# 24V_Multiphase_Buck.net
KiCad netlist of a schematic drawn in Altium Designer
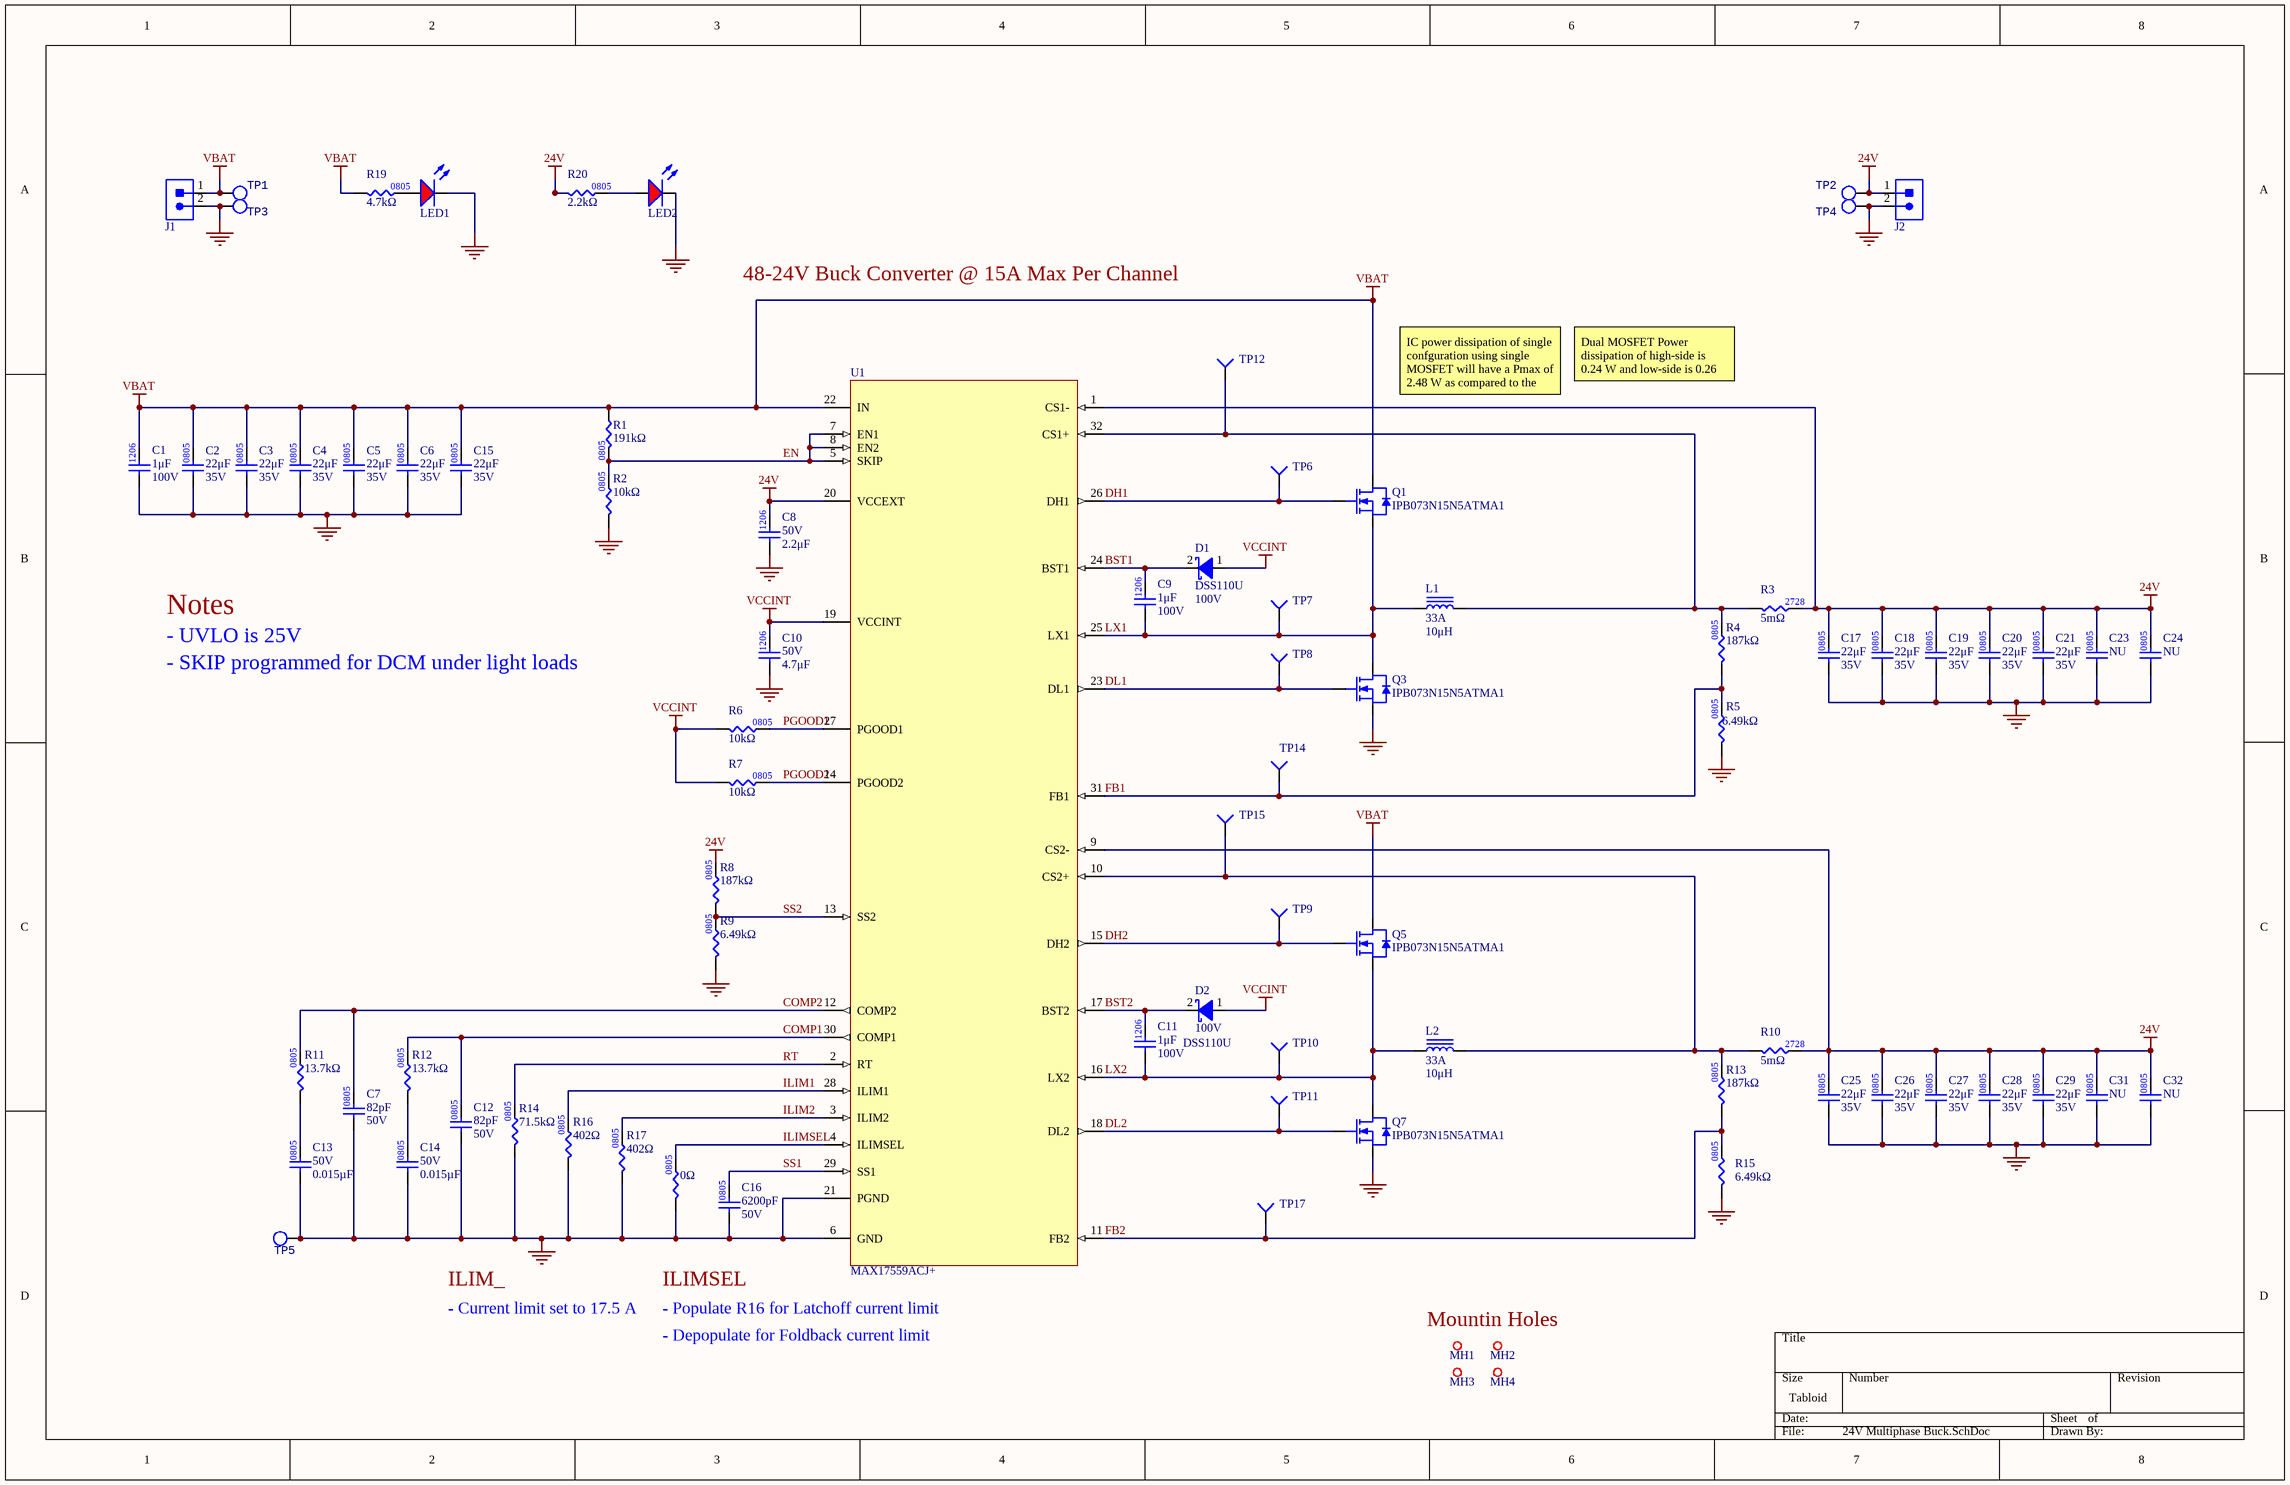
[diagram p0: 24V Multiphase Buck.SchDoc]

(export (version "E")
  (design (tool "Eeschema 10.0.6"))
  (components
    (comp (ref "C1")
      (value "1μF")
      (footprint "CAPC3216X190X50NL20T25")
      (description "CAP CER 1UF 100V X7R 1206")
      (fields (field (name "VOLTAGE RATING") "100V") (field (name "Comment") "CAP_1uF_100V_1206"))
      (libsource (lib "UWRT_Schematic_Library_2020") (part "CAP_1uF_100V_1206"))
    )
    (comp (ref "C2")
      (value "22μF")
      (footprint "CAP1206")
      (description "CAP CER 22UF 35V X5R 1206")
      (fields (field (name "VOLTAGE RATING") "35V") (field (name "Comment") "CAP_22uF_35V_1206"))
      (libsource (lib "UWRT_Schematic_Library_2020") (part "CAP_22uF_35V_1206"))
    )
    (comp (ref "C3")
      (value "22μF")
      (footprint "CAP1206")
      (description "CAP CER 22UF 35V X5R 1206")
      (fields (field (name "VOLTAGE RATING") "35V") (field (name "Comment") "CAP_22uF_35V_1206"))
      (libsource (lib "UWRT_Schematic_Library_2020") (part "CAP_22uF_35V_1206"))
    )
    (comp (ref "C4")
      (value "22μF")
      (footprint "CAP1206")
      (description "CAP CER 22UF 35V X5R 1206")
      (fields (field (name "VOLTAGE RATING") "35V") (field (name "Comment") "CAP_22uF_35V_1206"))
      (libsource (lib "UWRT_Schematic_Library_2020") (part "CAP_22uF_35V_1206"))
    )
    (comp (ref "C5")
      (value "22μF")
      (footprint "CAP1206")
      (description "CAP CER 22UF 35V X5R 1206")
      (fields (field (name "VOLTAGE RATING") "35V") (field (name "Comment") "CAP_22uF_35V_1206"))
      (libsource (lib "UWRT_Schematic_Library_2020") (part "CAP_22uF_35V_1206"))
    )
    (comp (ref "C6")
      (value "22μF")
      (footprint "CAP1206")
      (description "CAP CER 22UF 35V X5R 1206")
      (fields (field (name "VOLTAGE RATING") "35V") (field (name "Comment") "CAP_22uF_35V_1206"))
      (libsource (lib "UWRT_Schematic_Library_2020") (part "CAP_22uF_35V_1206"))
    )
    (comp (ref "C7")
      (value "82pF")
      (footprint "CAP0603")
      (description "CAP CER 82PF 50V C0G/NPO 0603")
      (fields (field (name "VOLTAGE RATING") "50V") (field (name "Comment") "CAP_82pF_50V_0603"))
      (libsource (lib "UWRT_Schematic_Library_2020") (part "CAP_82pF_50V_0603"))
    )
    (comp (ref "C8")
      (value "2.2μF")
      (footprint "CAP1206")
      (description "CAP CER 2.2UF 50V X7R 1206")
      (fields (field (name "VOLTAGE RATING") "50V") (field (name "Comment") "CAP_2.2uF_50V_1206"))
      (libsource (lib "UWRT_Schematic_Library_2020") (part "CAP_2.2uF_50V_1206"))
    )
    (comp (ref "C9")
      (value "1μF")
      (footprint "CAPC3216X190X50NL20T25")
      (description "CAP CER 1UF 100V X7R 1206")
      (fields (field (name "VOLTAGE RATING") "100V") (field (name "Comment") "CAP_1uF_100V_1206"))
      (libsource (lib "UWRT_Schematic_Library_2020") (part "CAP_1uF_100V_1206"))
    )
    (comp (ref "C10")
      (value "4.7μF")
      (footprint "CAP1206")
      (description "CAP CER 4.7UF 50V X7R 1206")
      (fields (field (name "VOLTAGE RATING") "50V") (field (name "Comment") "CAP_4.7uF_50V_1206"))
      (libsource (lib "UWRT_Schematic_Library_2020") (part "CAP_4.7uF_50V_1206"))
    )
    (comp (ref "C11")
      (value "1μF")
      (footprint "CAPC3216X190X50NL20T25")
      (description "CAP CER 1UF 100V X7R 1206")
      (fields (field (name "VOLTAGE RATING") "100V") (field (name "Comment") "CAP_1uF_100V_1206"))
      (libsource (lib "UWRT_Schematic_Library_2020") (part "CAP_1uF_100V_1206"))
    )
    (comp (ref "C12")
      (value "82pF")
      (footprint "CAP0603")
      (description "CAP CER 82PF 50V C0G/NPO 0603")
      (fields (field (name "VOLTAGE RATING") "50V") (field (name "Comment") "CAP_82pF_50V_0603"))
      (libsource (lib "UWRT_Schematic_Library_2020") (part "CAP_82pF_50V_0603"))
    )
    (comp (ref "C13")
      (value "0.015µF")
      (footprint "CAP0805")
      (description "CAP CER 0.015UF 50V C0G 0805")
      (fields (field (name "VOLTAGE RATING") "50V") (field (name "Comment") "CAP_0.015uF_50V_0805"))
      (libsource (lib "UWRT_Schematic_Library_2020") (part "CAP_0.015uF_50V_0805"))
    )
    (comp (ref "C14")
      (value "0.015µF")
      (footprint "CAP0805")
      (description "CAP CER 0.015UF 50V C0G 0805")
      (fields (field (name "VOLTAGE RATING") "50V") (field (name "Comment") "CAP_0.015uF_50V_0805"))
      (libsource (lib "UWRT_Schematic_Library_2020") (part "CAP_0.015uF_50V_0805"))
    )
    (comp (ref "C15")
      (value "22μF")
      (footprint "CAP1206")
      (description "CAP CER 22UF 35V X5R 1206")
      (fields (field (name "VOLTAGE RATING") "35V") (field (name "Comment") "CAP_22uF_35V_1206"))
      (libsource (lib "UWRT_Schematic_Library_2020") (part "CAP_22uF_35V_1206"))
    )
    (comp (ref "C16")
      (value "CAP_6200pF_50V_0805")
      (footprint "CAP0805")
      (description "CAP CER 6200PF 50V C0G/NP0 0805")
      (fields (field (name "CAPACITANCE") "6200pF") (field (name "VOLTAGE RATING") "50V"))
      (libsource (lib "UWRT_Schematic_Library_2020") (part "CAP_6200pF_50V_0805"))
    )
    (comp (ref "C17")
      (value "22μF")
      (footprint "CAP1206")
      (description "CAP CER 22UF 35V X5R 1206")
      (fields (field (name "VOLTAGE RATING") "35V") (field (name "Comment") "CAP_22uF_35V_1206"))
      (libsource (lib "UWRT_Schematic_Library_2020") (part "CAP_22uF_35V_1206"))
    )
    (comp (ref "C18")
      (value "22μF")
      (footprint "CAP1206")
      (description "CAP CER 22UF 35V X5R 1206")
      (fields (field (name "VOLTAGE RATING") "35V") (field (name "Comment") "CAP_22uF_35V_1206"))
      (libsource (lib "UWRT_Schematic_Library_2020") (part "CAP_22uF_35V_1206"))
    )
    (comp (ref "C19")
      (value "22μF")
      (footprint "CAP1206")
      (description "CAP CER 22UF 35V X5R 1206")
      (fields (field (name "VOLTAGE RATING") "35V") (field (name "Comment") "CAP_22uF_35V_1206"))
      (libsource (lib "UWRT_Schematic_Library_2020") (part "CAP_22uF_35V_1206"))
    )
    (comp (ref "C20")
      (value "22μF")
      (footprint "CAP1206")
      (description "CAP CER 22UF 35V X5R 1206")
      (fields (field (name "VOLTAGE RATING") "35V") (field (name "Comment") "CAP_22uF_35V_1206"))
      (libsource (lib "UWRT_Schematic_Library_2020") (part "CAP_22uF_35V_1206"))
    )
    (comp (ref "C21")
      (value "22μF")
      (footprint "CAP1206")
      (description "CAP CER 22UF 35V X5R 1206")
      (fields (field (name "VOLTAGE RATING") "35V") (field (name "Comment") "CAP_22uF_35V_1206"))
      (libsource (lib "UWRT_Schematic_Library_2020") (part "CAP_22uF_35V_1206"))
    )
    (comp (ref "C23")
      (value "NU")
      (footprint "CAP1206")
      (description "PLACEHOLDER CAPACITOR")
      (fields (field (name "Comment") "CAP_NU_1206"))
      (libsource (lib "UWRT_Schematic_Library_2020") (part "CAP_NU_1206"))
    )
    (comp (ref "C24")
      (value "NU")
      (footprint "CAP1206")
      (description "PLACEHOLDER CAPACITOR")
      (fields (field (name "Comment") "CAP_NU_1206"))
      (libsource (lib "UWRT_Schematic_Library_2020") (part "CAP_NU_1206"))
    )
    (comp (ref "C25")
      (value "22μF")
      (footprint "CAP1206")
      (description "CAP CER 22UF 35V X5R 1206")
      (fields (field (name "VOLTAGE RATING") "35V") (field (name "Comment") "CAP_22uF_35V_1206"))
      (libsource (lib "UWRT_Schematic_Library_2020") (part "CAP_22uF_35V_1206"))
    )
    (comp (ref "C26")
      (value "22μF")
      (footprint "CAP1206")
      (description "CAP CER 22UF 35V X5R 1206")
      (fields (field (name "VOLTAGE RATING") "35V") (field (name "Comment") "CAP_22uF_35V_1206"))
      (libsource (lib "UWRT_Schematic_Library_2020") (part "CAP_22uF_35V_1206"))
    )
    (comp (ref "C27")
      (value "22μF")
      (footprint "CAP1206")
      (description "CAP CER 22UF 35V X5R 1206")
      (fields (field (name "VOLTAGE RATING") "35V") (field (name "Comment") "CAP_22uF_35V_1206"))
      (libsource (lib "UWRT_Schematic_Library_2020") (part "CAP_22uF_35V_1206"))
    )
    (comp (ref "C28")
      (value "22μF")
      (footprint "CAP1206")
      (description "CAP CER 22UF 35V X5R 1206")
      (fields (field (name "VOLTAGE RATING") "35V") (field (name "Comment") "CAP_22uF_35V_1206"))
      (libsource (lib "UWRT_Schematic_Library_2020") (part "CAP_22uF_35V_1206"))
    )
    (comp (ref "C29")
      (value "22μF")
      (footprint "CAP1206")
      (description "CAP CER 22UF 35V X5R 1206")
      (fields (field (name "VOLTAGE RATING") "35V") (field (name "Comment") "CAP_22uF_35V_1206"))
      (libsource (lib "UWRT_Schematic_Library_2020") (part "CAP_22uF_35V_1206"))
    )
    (comp (ref "C31")
      (value "NU")
      (footprint "CAP1206")
      (description "PLACEHOLDER CAPACITOR")
      (fields (field (name "Comment") "CAP_NU_1206"))
      (libsource (lib "UWRT_Schematic_Library_2020") (part "CAP_NU_1206"))
    )
    (comp (ref "C32")
      (value "NU")
      (footprint "CAP1206")
      (description "PLACEHOLDER CAPACITOR")
      (fields (field (name "Comment") "CAP_NU_1206"))
      (libsource (lib "UWRT_Schematic_Library_2020") (part "CAP_NU_1206"))
    )
    (comp (ref "D1")
      (value "DIO_SCHOTTKY_100V_1A")
      (footprint "SOD-123FL")
      (description "DIODE SCHOTTKY 100V 1A SOD-123F")
      (fields (field (name "MANUFACTURER PART NUMBER 1") "DSS110U") (field (name "VR (MAX)") "100V"))
      (libsource (lib "UWRT_Schematic_Library_2020") (part "DIO_SCHOTTKY_100V_1A"))
    )
    (comp (ref "D2")
      (value "DIO_SCHOTTKY_100V_1A")
      (footprint "SOD-123FL")
      (description "DIODE SCHOTTKY 100V 1A SOD-123F")
      (fields (field (name "MANUFACTURER PART NUMBER 1") "DSS110U") (field (name "VR (MAX)") "100V"))
      (libsource (lib "UWRT_Schematic_Library_2020") (part "DIO_SCHOTTKY_100V_1A"))
    )
    (comp (ref "J1")
      (value "CON_2POS_SCREW_TERM")
      (footprint "CON_2POS_SCREW_TERM_65A")
      (description "PCB TERMINAL BLOCKS RISING CLAMP")
      (libsource (lib "UWRT_Schematic_Library_2020") (part "CON_2POS_SCREW_TERM_65A"))
    )
    (comp (ref "J2")
      (value "CON_2POS_SCREW_TERM")
      (footprint "CON_2POS_SCREW_TERM_65A")
      (description "PCB TERMINAL BLOCKS RISING CLAMP")
      (libsource (lib "") (part "CON_2POS_SCREW_TERM_65A_1"))
    )
    (comp (ref "L1")
      (value "IND_10uH_33A_SMD")
      (footprint "IND_B82559B7103A027")
      (description "FIXED IND 10UH 33A 1.92 MOHM SMD")
      (fields (field (name "CURRENT RATING") "33A") (field (name "INDUCTANCE") "10μH"))
      (libsource (lib "UWRT_Schematic_Library_2020") (part "IND_10uH_33A_SMD"))
    )
    (comp (ref "L2")
      (value "IND_10uH_33A_SMD")
      (footprint "IND_B82559B7103A027")
      (description "FIXED IND 10UH 33A 1.92 MOHM SMD")
      (fields (field (name "CURRENT RATING") "33A") (field (name "INDUCTANCE") "10μH"))
      (libsource (lib "UWRT_Schematic_Library_2020") (part "IND_10uH_33A_SMD"))
    )
    (comp (ref "LED1")
      (value "LED_RED")
      (footprint "LED_0805_RED")
      (description "LED RED DIFFUSED 0805 SMD")
      (libsource (lib "UWRT_Schematic_Library_2020") (part "LED_RED"))
    )
    (comp (ref "LED2")
      (value "LED_RED")
      (footprint "LED_0805_RED")
      (description "LED RED DIFFUSED 0805 SMD")
      (libsource (lib "UWRT_Schematic_Library_2020") (part "LED_RED"))
    )
    (comp (ref "MH1")
      (value "MOUNTING_HOLE_M3")
      (footprint "MOUNTING_HOLE_3mm")
      (libsource (lib "UWRT_Schematic_Library_2020") (part "MOUNTING_HOLE_M3"))
    )
    (comp (ref "MH2")
      (value "MOUNTING_HOLE_M3")
      (footprint "MOUNTING_HOLE_3mm")
      (libsource (lib "UWRT_Schematic_Library_2020") (part "MOUNTING_HOLE_M3"))
    )
    (comp (ref "MH3")
      (value "MOUNTING_HOLE_M3")
      (footprint "MOUNTING_HOLE_3mm")
      (libsource (lib "UWRT_Schematic_Library_2020") (part "MOUNTING_HOLE_M3"))
    )
    (comp (ref "MH4")
      (value "MOUNTING_HOLE_M3")
      (footprint "MOUNTING_HOLE_3mm")
      (libsource (lib "UWRT_Schematic_Library_2020") (part "MOUNTING_HOLE_M3"))
    )
    (comp (ref "Q1")
      (value "NMOS_150V_114A")
      (footprint "NMOS_DPAK263-3-2")
      (description "MOSFET N-CH 150V 114A TO263-3")
      (fields (field (name "MANUFACTURER PART NUMBER 1") "IPB073N15N5ATMA1"))
      (libsource (lib "UWRT_Schematic_Library_2020") (part "NMOS_150V_114A"))
    )
    (comp (ref "Q3")
      (value "NMOS_150V_114A")
      (footprint "NMOS_DPAK263-3-2")
      (description "MOSFET N-CH 150V 114A TO263-3")
      (fields (field (name "MANUFACTURER PART NUMBER 1") "IPB073N15N5ATMA1"))
      (libsource (lib "UWRT_Schematic_Library_2020") (part "NMOS_150V_114A"))
    )
    (comp (ref "Q5")
      (value "NMOS_150V_114A")
      (footprint "NMOS_DPAK263-3-2")
      (description "MOSFET N-CH 150V 114A TO263-3")
      (fields (field (name "MANUFACTURER PART NUMBER 1") "IPB073N15N5ATMA1"))
      (libsource (lib "UWRT_Schematic_Library_2020") (part "NMOS_150V_114A"))
    )
    (comp (ref "Q7")
      (value "NMOS_150V_114A")
      (footprint "NMOS_DPAK263-3-2")
      (description "MOSFET N-CH 150V 114A TO263-3")
      (fields (field (name "MANUFACTURER PART NUMBER 1") "IPB073N15N5ATMA1"))
      (libsource (lib "UWRT_Schematic_Library_2020") (part "NMOS_150V_114A"))
    )
    (comp (ref "R1")
      (value "191kΩ")
      (footprint "RES0805")
      (description "RES 191K OHM 1% 1/8W 0805")
      (fields (field (name "Comment") "RES_191kΩ_0805_1%"))
      (libsource (lib "UWRT_Schematic_Library_2020") (part "RES_191kΩ_0805_1%"))
    )
    (comp (ref "R2")
      (value "10kΩ")
      (footprint "RES0805")
      (description "RES 10K OHM 5% 1/8W 0805")
      (fields (field (name "LCSC PART #") "C17414") (field (name "Comment") "RES_10kΩ_0805_5%"))
      (libsource (lib "UWRT_Schematic_Library_2020") (part "RES_10kΩ_0805_5%"))
    )
    (comp (ref "R3")
      (value "5mΩ")
      (footprint "RES2728")
      (description "RES 0.005 OHM 1% 4W 2827")
      (fields (field (name "Comment") "RES_5mΩ_2728_1%"))
      (libsource (lib "UWRT_Schematic_Library_2020") (part "RES_5mΩ_2728_1%"))
    )
    (comp (ref "R4")
      (value "187kΩ")
      (footprint "RES0805")
      (description "RES 187K OHM 0.1% 1/8W 0805")
      (fields (field (name "Comment") "RES_187kΩ_0805_0.1%"))
      (libsource (lib "UWRT_Schematic_Library_2020") (part "RES_187kΩ_0805_0.1%"))
    )
    (comp (ref "R5")
      (value "6.49kΩ")
      (footprint "RES0805")
      (description "RES 6.49K OHM 1% 1/8W 0805")
      (fields (field (name "Comment") "RES_6.49kΩ_0805_1%"))
      (libsource (lib "UWRT_Schematic_Library_2020") (part "RES_6.49kΩ_0805_1%"))
    )
    (comp (ref "R6")
      (value "10kΩ")
      (footprint "RES0805")
      (description "RES 10K OHM 5% 1/8W 0805")
      (fields (field (name "LCSC PART #") "C17414") (field (name "Comment") "RES_10kΩ_0805_5%"))
      (libsource (lib "UWRT_Schematic_Library_2020") (part "RES_10kΩ_0805_5%"))
    )
    (comp (ref "R7")
      (value "10kΩ")
      (footprint "RES0805")
      (description "RES 10K OHM 5% 1/8W 0805")
      (fields (field (name "LCSC PART #") "C17414") (field (name "Comment") "RES_10kΩ_0805_5%"))
      (libsource (lib "UWRT_Schematic_Library_2020") (part "RES_10kΩ_0805_5%"))
    )
    (comp (ref "R8")
      (value "187kΩ")
      (footprint "RES0805")
      (description "RES 187K OHM 0.1% 1/8W 0805")
      (fields (field (name "Comment") "RES_187kΩ_0805_0.1%"))
      (libsource (lib "UWRT_Schematic_Library_2020") (part "RES_187kΩ_0805_0.1%"))
    )
    (comp (ref "R9")
      (value "6.49kΩ")
      (footprint "RES0805")
      (description "RES 6.49K OHM 1% 1/8W 0805")
      (fields (field (name "Comment") "RES_6.49kΩ_0805_1%"))
      (libsource (lib "UWRT_Schematic_Library_2020") (part "RES_6.49kΩ_0805_1%"))
    )
    (comp (ref "R10")
      (value "5mΩ")
      (footprint "RES2728")
      (description "RES 0.005 OHM 1% 4W 2827")
      (fields (field (name "Comment") "RES_5mΩ_2728_1%"))
      (libsource (lib "UWRT_Schematic_Library_2020") (part "RES_5mΩ_2728_1%"))
    )
    (comp (ref "R11")
      (value "13.7kΩ")
      (footprint "RES0805")
      (description "RES 13.7K OHM 1% 1/8W 0805")
      (fields (field (name "LCSC PART #") "C17448") (field (name "Comment") "RES_13.7kΩ_0805_1%"))
      (libsource (lib "UWRT_Schematic_Library_2020") (part "RES_13.7kΩ_0805_1%"))
    )
    (comp (ref "R12")
      (value "13.7kΩ")
      (footprint "RES0805")
      (description "RES 13.7K OHM 1% 1/8W 0805")
      (fields (field (name "LCSC PART #") "C17448") (field (name "Comment") "RES_13.7kΩ_0805_1%"))
      (libsource (lib "UWRT_Schematic_Library_2020") (part "RES_13.7kΩ_0805_1%"))
    )
    (comp (ref "R13")
      (value "187kΩ")
      (footprint "RES0805")
      (description "RES 187K OHM 0.1% 1/8W 0805")
      (fields (field (name "Comment") "RES_187kΩ_0805_0.1%"))
      (libsource (lib "UWRT_Schematic_Library_2020") (part "RES_187kΩ_0805_0.1%"))
    )
    (comp (ref "R14")
      (value "71.5kΩ")
      (footprint "RES0805")
      (description "RES 71.5K OHM 1% 1/8W 0805")
      (fields (field (name "Comment") "RES_71.5kΩ_0805_1%"))
      (libsource (lib "UWRT_Schematic_Library_2020") (part "RES_71.5kΩ_0805_1%"))
    )
    (comp (ref "R15")
      (value "6.49kΩ")
      (footprint "RES0805")
      (description "RES 6.49K OHM 1% 1/8W 0805")
      (fields (field (name "Comment") "RES_6.49kΩ_0805_1%"))
      (libsource (lib "UWRT_Schematic_Library_2020") (part "RES_6.49kΩ_0805_1%"))
    )
    (comp (ref "R16")
      (value "402Ω")
      (footprint "RES0805")
      (description "RES 402 OHM 1% 1/8W 0805")
      (fields (field (name "LCSC PART #") "C17681") (field (name "Comment") "RES_402Ω_0805_1%"))
      (libsource (lib "UWRT_Schematic_Library_2020") (part "RES_402Ω_0805_1%"))
    )
    (comp (ref "R17")
      (value "402Ω")
      (footprint "RES0805")
      (description "RES 402 OHM 1% 1/8W 0805")
      (fields (field (name "LCSC PART #") "C17681") (field (name "Comment") "RES_402Ω_0805_1%"))
      (libsource (lib "UWRT_Schematic_Library_2020") (part "RES_402Ω_0805_1%"))
    )
    (comp (ref "R18")
      (value "0Ω")
      (footprint "RES0805")
      (description "RES 0 OHM JUMPER 1/8W 0805")
      (fields (field (name "Comment") "RES_0Ω_0805"))
      (libsource (lib "UWRT_Schematic_Library_2020") (part "RES_0Ω_0805"))
    )
    (comp (ref "R19")
      (value "4.7kΩ")
      (footprint "RES0805")
      (description "RES 4.7K OHM 5% 1/8W 0805")
      (fields (field (name "LCSC PART #") "C17673") (field (name "Comment") "RES_4.7kΩ_0805_5%"))
      (libsource (lib "UWRT_Schematic_Library_2020") (part "RES_4.7kΩ_0805_5%"))
    )
    (comp (ref "R20")
      (value "2.2kΩ")
      (footprint "RES0805")
      (description "RES 2.2K OHM 5% 1/8W 0805")
      (fields (field (name "TOLERANCE") "5%") (field (name "Comment") "RES_2.2kΩ_0805_5%"))
      (libsource (lib "UWRT_Schematic_Library_2020") (part "RES_2.2kΩ_0805_5%"))
    )
    (comp (ref "TP1")
      (value "TESTPOINT_LOOP")
      (footprint "TESTPOINT_LOOP")
      (description "TESTPOINT THRUHOLE")
      (libsource (lib "UWRT_Schematic_Library_2020") (part "TESTPOINT_LOOP"))
    )
    (comp (ref "TP2")
      (value "TESTPOINT_LOOP")
      (footprint "TESTPOINT_LOOP")
      (description "TESTPOINT THRUHOLE")
      (libsource (lib "UWRT_Schematic_Library_2020") (part "TESTPOINT_LOOP"))
    )
    (comp (ref "TP3")
      (value "TESTPOINT_LOOP")
      (footprint "TESTPOINT_LOOP")
      (description "TESTPOINT THRUHOLE")
      (libsource (lib "UWRT_Schematic_Library_2020") (part "TESTPOINT_LOOP"))
    )
    (comp (ref "TP4")
      (value "TESTPOINT_LOOP")
      (footprint "TESTPOINT_LOOP")
      (description "TESTPOINT THRUHOLE")
      (libsource (lib "UWRT_Schematic_Library_2020") (part "TESTPOINT_LOOP"))
    )
    (comp (ref "TP5")
      (value "TESTPOINT_LOOP")
      (footprint "TESTPOINT_LOOP")
      (description "TESTPOINT THRUHOLE")
      (libsource (lib "UWRT_Schematic_Library_2020") (part "TESTPOINT_LOOP"))
    )
    (comp (ref "TP6")
      (value "TESTPOINT_1MM_CIRCLE")
      (footprint "TESTPOINT_CIRCLE_1MM")
      (description "TESTPOINT 1MM CIRCLE")
      (libsource (lib "UWRT_Schematic_Library_2020") (part "TESTPOINT_1MM_CIRCLE"))
    )
    (comp (ref "TP7")
      (value "TESTPOINT_1MM_CIRCLE")
      (footprint "TESTPOINT_CIRCLE_1MM")
      (description "TESTPOINT 1MM CIRCLE")
      (libsource (lib "UWRT_Schematic_Library_2020") (part "TESTPOINT_1MM_CIRCLE"))
    )
    (comp (ref "TP8")
      (value "TESTPOINT_1MM_CIRCLE")
      (footprint "TESTPOINT_CIRCLE_1MM")
      (description "TESTPOINT 1MM CIRCLE")
      (libsource (lib "UWRT_Schematic_Library_2020") (part "TESTPOINT_1MM_CIRCLE"))
    )
    (comp (ref "TP9")
      (value "TESTPOINT_1MM_CIRCLE")
      (footprint "TESTPOINT_CIRCLE_1MM")
      (description "TESTPOINT 1MM CIRCLE")
      (libsource (lib "UWRT_Schematic_Library_2020") (part "TESTPOINT_1MM_CIRCLE"))
    )
    (comp (ref "TP10")
      (value "TESTPOINT_1MM_CIRCLE")
      (footprint "TESTPOINT_CIRCLE_1MM")
      (description "TESTPOINT 1MM CIRCLE")
      (libsource (lib "UWRT_Schematic_Library_2020") (part "TESTPOINT_1MM_CIRCLE"))
    )
    (comp (ref "TP11")
      (value "TESTPOINT_1MM_CIRCLE")
      (footprint "TESTPOINT_CIRCLE_1MM")
      (description "TESTPOINT 1MM CIRCLE")
      (libsource (lib "UWRT_Schematic_Library_2020") (part "TESTPOINT_1MM_CIRCLE"))
    )
    (comp (ref "TP12")
      (value "TESTPOINT_1MM_CIRCLE")
      (footprint "TESTPOINT_CIRCLE_1MM")
      (description "TESTPOINT 1MM CIRCLE")
      (libsource (lib "UWRT_Schematic_Library_2020") (part "TESTPOINT_1MM_CIRCLE"))
    )
    (comp (ref "TP14")
      (value "TESTPOINT_1MM_CIRCLE")
      (footprint "TESTPOINT_CIRCLE_1MM")
      (description "TESTPOINT 1MM CIRCLE")
      (libsource (lib "UWRT_Schematic_Library_2020") (part "TESTPOINT_1MM_CIRCLE"))
    )
    (comp (ref "TP15")
      (value "TESTPOINT_1MM_CIRCLE")
      (footprint "TESTPOINT_CIRCLE_1MM")
      (description "TESTPOINT 1MM CIRCLE")
      (libsource (lib "UWRT_Schematic_Library_2020") (part "TESTPOINT_1MM_CIRCLE"))
    )
    (comp (ref "TP17")
      (value "TESTPOINT_1MM_CIRCLE")
      (footprint "TESTPOINT_CIRCLE_1MM")
      (description "TESTPOINT 1MM CIRCLE")
      (libsource (lib "UWRT_Schematic_Library_2020") (part "TESTPOINT_1MM_CIRCLE"))
    )
    (comp (ref "U1")
      (value "MAX17559ACJ+")
      (footprint "IC_32-TQFP")
      (description "IC REG CTRLR BUCK 32TQFP")
      (libsource (lib "UWRT_Schematic_Library_2020") (part "MAX17559ACJ+"))
    )
  )
  (nets
    (net (code "1") (name "/BST1") (class "Default")
      (node (ref "C9") (pin "2") (pinfunction "2_2") (pintype "passive"))
      (node (ref "D1") (pin "2") (pinfunction "Cathode_2") (pintype "passive"))
      (node (ref "U1") (pin "24") (pinfunction "BST1_24") (pintype "input"))
    )
    (net (code "2") (name "/BST2") (class "Default")
      (node (ref "C11") (pin "2") (pinfunction "2_2") (pintype "passive"))
      (node (ref "D2") (pin "2") (pinfunction "Cathode_2") (pintype "passive"))
      (node (ref "U1") (pin "17") (pinfunction "BST2_17") (pintype "input"))
    )
    (net (code "3") (name "/COMP1") (class "Default")
      (node (ref "C12") (pin "2") (pinfunction "2_2") (pintype "passive"))
      (node (ref "R12") (pin "2") (pinfunction "2_2") (pintype "passive"))
      (node (ref "U1") (pin "30") (pinfunction "COMP1_30") (pintype "output"))
    )
    (net (code "4") (name "/COMP2") (class "Default")
      (node (ref "C7") (pin "2") (pinfunction "2_2") (pintype "passive"))
      (node (ref "R11") (pin "2") (pinfunction "2_2") (pintype "passive"))
      (node (ref "U1") (pin "12") (pinfunction "COMP2_12") (pintype "output"))
    )
    (net (code "5") (name "/DH1") (class "Default")
      (node (ref "Q1") (pin "1") (pinfunction "GATE_1") (pintype "passive"))
      (node (ref "TP6") (pin "1") (pinfunction "=value_1") (pintype "passive"))
      (node (ref "U1") (pin "26") (pinfunction "DH1_26") (pintype "output"))
    )
    (net (code "6") (name "/DH2") (class "Default")
      (node (ref "Q5") (pin "1") (pinfunction "GATE_1") (pintype "passive"))
      (node (ref "TP9") (pin "1") (pinfunction "=value_1") (pintype "passive"))
      (node (ref "U1") (pin "15") (pinfunction "DH2_15") (pintype "output"))
    )
    (net (code "7") (name "/DL1") (class "Default")
      (node (ref "Q3") (pin "1") (pinfunction "GATE_1") (pintype "passive"))
      (node (ref "TP8") (pin "1") (pinfunction "=value_1") (pintype "passive"))
      (node (ref "U1") (pin "23") (pinfunction "DL1_23") (pintype "output"))
    )
    (net (code "8") (name "/DL2") (class "Default")
      (node (ref "Q7") (pin "1") (pinfunction "GATE_1") (pintype "passive"))
      (node (ref "TP11") (pin "1") (pinfunction "=value_1") (pintype "passive"))
      (node (ref "U1") (pin "18") (pinfunction "DL2_18") (pintype "output"))
    )
    (net (code "9") (name "/EN") (class "Default")
      (node (ref "R1") (pin "1") (pinfunction "1_1") (pintype "passive"))
      (node (ref "R2") (pin "2") (pinfunction "2_2") (pintype "passive"))
      (node (ref "U1") (pin "5") (pinfunction "SKIP_5") (pintype "input"))
      (node (ref "U1") (pin "7") (pinfunction "EN1_7") (pintype "input"))
      (node (ref "U1") (pin "8") (pinfunction "EN2_8") (pintype "input"))
    )
    (net (code "10") (name "/FB1") (class "Default")
      (node (ref "R4") (pin "1") (pinfunction "1_1") (pintype "passive"))
      (node (ref "R5") (pin "2") (pinfunction "2_2") (pintype "passive"))
      (node (ref "TP14") (pin "1") (pinfunction "=value_1") (pintype "passive"))
      (node (ref "U1") (pin "31") (pinfunction "FB1_31") (pintype "input"))
    )
    (net (code "11") (name "/FB2") (class "Default")
      (node (ref "R13") (pin "1") (pinfunction "1_1") (pintype "passive"))
      (node (ref "R15") (pin "2") (pinfunction "2_2") (pintype "passive"))
      (node (ref "TP17") (pin "1") (pinfunction "=value_1") (pintype "passive"))
      (node (ref "U1") (pin "11") (pinfunction "FB2_11") (pintype "input"))
    )
    (net (code "12") (name "/ILIM1") (class "Default")
      (node (ref "R16") (pin "2") (pinfunction "2_2") (pintype "passive"))
      (node (ref "U1") (pin "28") (pinfunction "ILIM1_28") (pintype "input"))
    )
    (net (code "13") (name "/ILIM2") (class "Default")
      (node (ref "R17") (pin "2") (pinfunction "2_2") (pintype "passive"))
      (node (ref "U1") (pin "3") (pinfunction "ILIM2_3") (pintype "input"))
    )
    (net (code "14") (name "/ILIMSEL") (class "Default")
      (node (ref "R18") (pin "2") (pinfunction "2_2") (pintype "passive"))
      (node (ref "U1") (pin "4") (pinfunction "ILIMSEL_4") (pintype "input"))
    )
    (net (code "15") (name "/LX1") (class "Default")
      (node (ref "C9") (pin "1") (pinfunction "1_1") (pintype "passive"))
      (node (ref "L1") (pin "1") (pinfunction "1_1") (pintype "passive"))
      (node (ref "Q1") (pin "3") (pinfunction "SOURCE_3") (pintype "passive"))
      (node (ref "Q3") (pin "2") (pinfunction "DRAIN_2") (pintype "passive"))
      (node (ref "TP7") (pin "1") (pinfunction "=value_1") (pintype "passive"))
      (node (ref "U1") (pin "25") (pinfunction "LX1_25") (pintype "input"))
    )
    (net (code "16") (name "/LX2") (class "Default")
      (node (ref "C11") (pin "1") (pinfunction "1_1") (pintype "passive"))
      (node (ref "L2") (pin "1") (pinfunction "1_1") (pintype "passive"))
      (node (ref "Q5") (pin "3") (pinfunction "SOURCE_3") (pintype "passive"))
      (node (ref "Q7") (pin "2") (pinfunction "DRAIN_2") (pintype "passive"))
      (node (ref "TP10") (pin "1") (pinfunction "=value_1") (pintype "passive"))
      (node (ref "U1") (pin "16") (pinfunction "LX2_16") (pintype "input"))
    )
    (net (code "17") (name "/PGOOD1") (class "Default")
      (node (ref "R6") (pin "2") (pinfunction "2_2") (pintype "passive"))
      (node (ref "U1") (pin "27") (pinfunction "PGOOD1_27") (pintype "open_collector"))
    )
    (net (code "18") (name "/PGOOD2") (class "Default")
      (node (ref "R7") (pin "2") (pinfunction "2_2") (pintype "passive"))
      (node (ref "U1") (pin "14") (pinfunction "PGOOD2_14") (pintype "open_collector"))
    )
    (net (code "19") (name "/RT") (class "Default")
      (node (ref "R14") (pin "2") (pinfunction "2_2") (pintype "passive"))
      (node (ref "U1") (pin "2") (pinfunction "RT_2") (pintype "input"))
    )
    (net (code "20") (name "/SS1") (class "Default")
      (node (ref "C16") (pin "2") (pinfunction "2_2") (pintype "passive"))
      (node (ref "U1") (pin "29") (pinfunction "SS1_29") (pintype "input"))
    )
    (net (code "21") (name "/SS2") (class "Default")
      (node (ref "R8") (pin "1") (pinfunction "1_1") (pintype "passive"))
      (node (ref "R9") (pin "2") (pinfunction "2_2") (pintype "passive"))
      (node (ref "U1") (pin "13") (pinfunction "SS2_13") (pintype "input"))
    )
    (net (code "22") (name "24V") (class "Default")
      (node (ref "C17") (pin "2") (pinfunction "2_2") (pintype "passive"))
      (node (ref "C18") (pin "2") (pinfunction "2_2") (pintype "passive"))
      (node (ref "C19") (pin "2") (pinfunction "2_2") (pintype "passive"))
      (node (ref "C20") (pin "2") (pinfunction "2_2") (pintype "passive"))
      (node (ref "C21") (pin "2") (pinfunction "2_2") (pintype "passive"))
      (node (ref "C23") (pin "2") (pinfunction "2_2") (pintype "passive"))
      (node (ref "C24") (pin "2") (pinfunction "2_2") (pintype "passive"))
      (node (ref "C25") (pin "2") (pinfunction "2_2") (pintype "passive"))
      (node (ref "C26") (pin "2") (pinfunction "2_2") (pintype "passive"))
      (node (ref "C27") (pin "2") (pinfunction "2_2") (pintype "passive"))
      (node (ref "C28") (pin "2") (pinfunction "2_2") (pintype "passive"))
      (node (ref "C29") (pin "2") (pinfunction "2_2") (pintype "passive"))
      (node (ref "C31") (pin "2") (pinfunction "2_2") (pintype "passive"))
      (node (ref "C32") (pin "2") (pinfunction "2_2") (pintype "passive"))
      (node (ref "C8") (pin "2") (pinfunction "2_2") (pintype "passive"))
      (node (ref "J2") (pin "1") (pinfunction "1_1") (pintype "passive"))
      (node (ref "R10") (pin "2") (pinfunction "2_2") (pintype "passive"))
      (node (ref "R20") (pin "1") (pinfunction "1_1") (pintype "passive"))
      (node (ref "R3") (pin "2") (pinfunction "2_2") (pintype "passive"))
      (node (ref "R8") (pin "2") (pinfunction "2_2") (pintype "passive"))
      (node (ref "TP2") (pin "1") (pintype "passive"))
      (node (ref "U1") (pin "1") (pinfunction "CS1-_1") (pintype "input"))
      (node (ref "U1") (pin "20") (pinfunction "VCCEXT_20") (pintype "power_in"))
      (node (ref "U1") (pin "9") (pinfunction "CS2-_9") (pintype "input"))
    )
    (net (code "23") (name "GND") (class "Default")
      (node (ref "C1") (pin "1") (pinfunction "1_1") (pintype "passive"))
      (node (ref "C10") (pin "1") (pinfunction "1_1") (pintype "passive"))
      (node (ref "C12") (pin "1") (pinfunction "1_1") (pintype "passive"))
      (node (ref "C13") (pin "1") (pinfunction "1_1") (pintype "passive"))
      (node (ref "C14") (pin "1") (pinfunction "1_1") (pintype "passive"))
      (node (ref "C15") (pin "1") (pinfunction "1_1") (pintype "passive"))
      (node (ref "C16") (pin "1") (pinfunction "1_1") (pintype "passive"))
      (node (ref "C17") (pin "1") (pinfunction "1_1") (pintype "passive"))
      (node (ref "C18") (pin "1") (pinfunction "1_1") (pintype "passive"))
      (node (ref "C19") (pin "1") (pinfunction "1_1") (pintype "passive"))
      (node (ref "C2") (pin "1") (pinfunction "1_1") (pintype "passive"))
      (node (ref "C20") (pin "1") (pinfunction "1_1") (pintype "passive"))
      (node (ref "C21") (pin "1") (pinfunction "1_1") (pintype "passive"))
      (node (ref "C23") (pin "1") (pinfunction "1_1") (pintype "passive"))
      (node (ref "C24") (pin "1") (pinfunction "1_1") (pintype "passive"))
      (node (ref "C25") (pin "1") (pinfunction "1_1") (pintype "passive"))
      (node (ref "C26") (pin "1") (pinfunction "1_1") (pintype "passive"))
      (node (ref "C27") (pin "1") (pinfunction "1_1") (pintype "passive"))
      (node (ref "C28") (pin "1") (pinfunction "1_1") (pintype "passive"))
      (node (ref "C29") (pin "1") (pinfunction "1_1") (pintype "passive"))
      (node (ref "C3") (pin "1") (pinfunction "1_1") (pintype "passive"))
      (node (ref "C31") (pin "1") (pinfunction "1_1") (pintype "passive"))
      (node (ref "C32") (pin "1") (pinfunction "1_1") (pintype "passive"))
      (node (ref "C4") (pin "1") (pinfunction "1_1") (pintype "passive"))
      (node (ref "C5") (pin "1") (pinfunction "1_1") (pintype "passive"))
      (node (ref "C6") (pin "1") (pinfunction "1_1") (pintype "passive"))
      (node (ref "C7") (pin "1") (pinfunction "1_1") (pintype "passive"))
      (node (ref "C8") (pin "1") (pinfunction "1_1") (pintype "passive"))
      (node (ref "J1") (pin "2") (pinfunction "2_2") (pintype "passive"))
      (node (ref "J2") (pin "2") (pinfunction "2_2") (pintype "passive"))
      (node (ref "LED1") (pin "2") (pinfunction "K_2") (pintype "passive"))
      (node (ref "LED2") (pin "2") (pinfunction "K_2") (pintype "passive"))
      (node (ref "Q3") (pin "3") (pinfunction "SOURCE_3") (pintype "passive"))
      (node (ref "Q7") (pin "3") (pinfunction "SOURCE_3") (pintype "passive"))
      (node (ref "R14") (pin "1") (pinfunction "1_1") (pintype "passive"))
      (node (ref "R15") (pin "1") (pinfunction "1_1") (pintype "passive"))
      (node (ref "R16") (pin "1") (pinfunction "1_1") (pintype "passive"))
      (node (ref "R17") (pin "1") (pinfunction "1_1") (pintype "passive"))
      (node (ref "R18") (pin "1") (pinfunction "1_1") (pintype "passive"))
      (node (ref "R2") (pin "1") (pinfunction "1_1") (pintype "passive"))
      (node (ref "R5") (pin "1") (pinfunction "1_1") (pintype "passive"))
      (node (ref "R9") (pin "1") (pinfunction "1_1") (pintype "passive"))
      (node (ref "TP3") (pin "1") (pintype "passive"))
      (node (ref "TP4") (pin "1") (pintype "passive"))
      (node (ref "TP5") (pin "1") (pintype "passive"))
      (node (ref "U1") (pin "21") (pinfunction "PGND_21") (pintype "power_in"))
      (node (ref "U1") (pin "6") (pinfunction "GND_6") (pintype "power_in"))
    )
    (net (code "24") (name "Net-(C13-Pad2)") (class "Default")
      (node (ref "C13") (pin "2") (pinfunction "2_2") (pintype "passive"))
      (node (ref "R11") (pin "1") (pinfunction "1_1") (pintype "passive"))
    )
    (net (code "25") (name "Net-(C14-Pad2)") (class "Default")
      (node (ref "C14") (pin "2") (pinfunction "2_2") (pintype "passive"))
      (node (ref "R12") (pin "1") (pinfunction "1_1") (pintype "passive"))
    )
    (net (code "26") (name "Net-(LED1-A)") (class "Default")
      (node (ref "LED1") (pin "1") (pinfunction "A_1") (pintype "passive"))
      (node (ref "R19") (pin "2") (pinfunction "2_2") (pintype "passive"))
    )
    (net (code "27") (name "Net-(LED2-A)") (class "Default")
      (node (ref "LED2") (pin "1") (pinfunction "A_1") (pintype "passive"))
      (node (ref "R20") (pin "2") (pinfunction "2_2") (pintype "passive"))
    )
    (net (code "28") (name "Net-(TP12-=value)") (class "Default")
      (node (ref "L1") (pin "2") (pinfunction "2_2") (pintype "passive"))
      (node (ref "R3") (pin "1") (pinfunction "1_1") (pintype "passive"))
      (node (ref "R4") (pin "2") (pinfunction "2_2") (pintype "passive"))
      (node (ref "TP12") (pin "1") (pinfunction "=value_1") (pintype "passive"))
      (node (ref "U1") (pin "32") (pinfunction "CS1+_32") (pintype "input"))
    )
    (net (code "29") (name "Net-(TP15-=value)") (class "Default")
      (node (ref "L2") (pin "2") (pinfunction "2_2") (pintype "passive"))
      (node (ref "R10") (pin "1") (pinfunction "1_1") (pintype "passive"))
      (node (ref "R13") (pin "2") (pinfunction "2_2") (pintype "passive"))
      (node (ref "TP15") (pin "1") (pinfunction "=value_1") (pintype "passive"))
      (node (ref "U1") (pin "10") (pinfunction "CS2+_10") (pintype "input"))
    )
    (net (code "30") (name "VBAT") (class "Default")
      (node (ref "C1") (pin "2") (pinfunction "2_2") (pintype "passive"))
      (node (ref "C15") (pin "2") (pinfunction "2_2") (pintype "passive"))
      (node (ref "C2") (pin "2") (pinfunction "2_2") (pintype "passive"))
      (node (ref "C3") (pin "2") (pinfunction "2_2") (pintype "passive"))
      (node (ref "C4") (pin "2") (pinfunction "2_2") (pintype "passive"))
      (node (ref "C5") (pin "2") (pinfunction "2_2") (pintype "passive"))
      (node (ref "C6") (pin "2") (pinfunction "2_2") (pintype "passive"))
      (node (ref "J1") (pin "1") (pinfunction "1_1") (pintype "passive"))
      (node (ref "Q1") (pin "2") (pinfunction "DRAIN_2") (pintype "passive"))
      (node (ref "Q5") (pin "2") (pinfunction "DRAIN_2") (pintype "passive"))
      (node (ref "R1") (pin "2") (pinfunction "2_2") (pintype "passive"))
      (node (ref "R19") (pin "1") (pinfunction "1_1") (pintype "passive"))
      (node (ref "TP1") (pin "1") (pintype "passive"))
      (node (ref "U1") (pin "22") (pinfunction "IN_22") (pintype "power_in"))
    )
    (net (code "31") (name "VCCINT") (class "Default")
      (node (ref "C10") (pin "2") (pinfunction "2_2") (pintype "passive"))
      (node (ref "D1") (pin "1") (pinfunction "Anode_1") (pintype "passive"))
      (node (ref "D2") (pin "1") (pinfunction "Anode_1") (pintype "passive"))
      (node (ref "R6") (pin "1") (pinfunction "1_1") (pintype "passive"))
      (node (ref "R7") (pin "1") (pinfunction "1_1") (pintype "passive"))
      (node (ref "U1") (pin "19") (pinfunction "VCCINT_19") (pintype "power_in"))
    )
  )
)
